# openSX70_SONAR-FBW_8-9-3-8-S4-TCS3200-NO.net
KiCad netlist of a schematic drawn in EAGLE
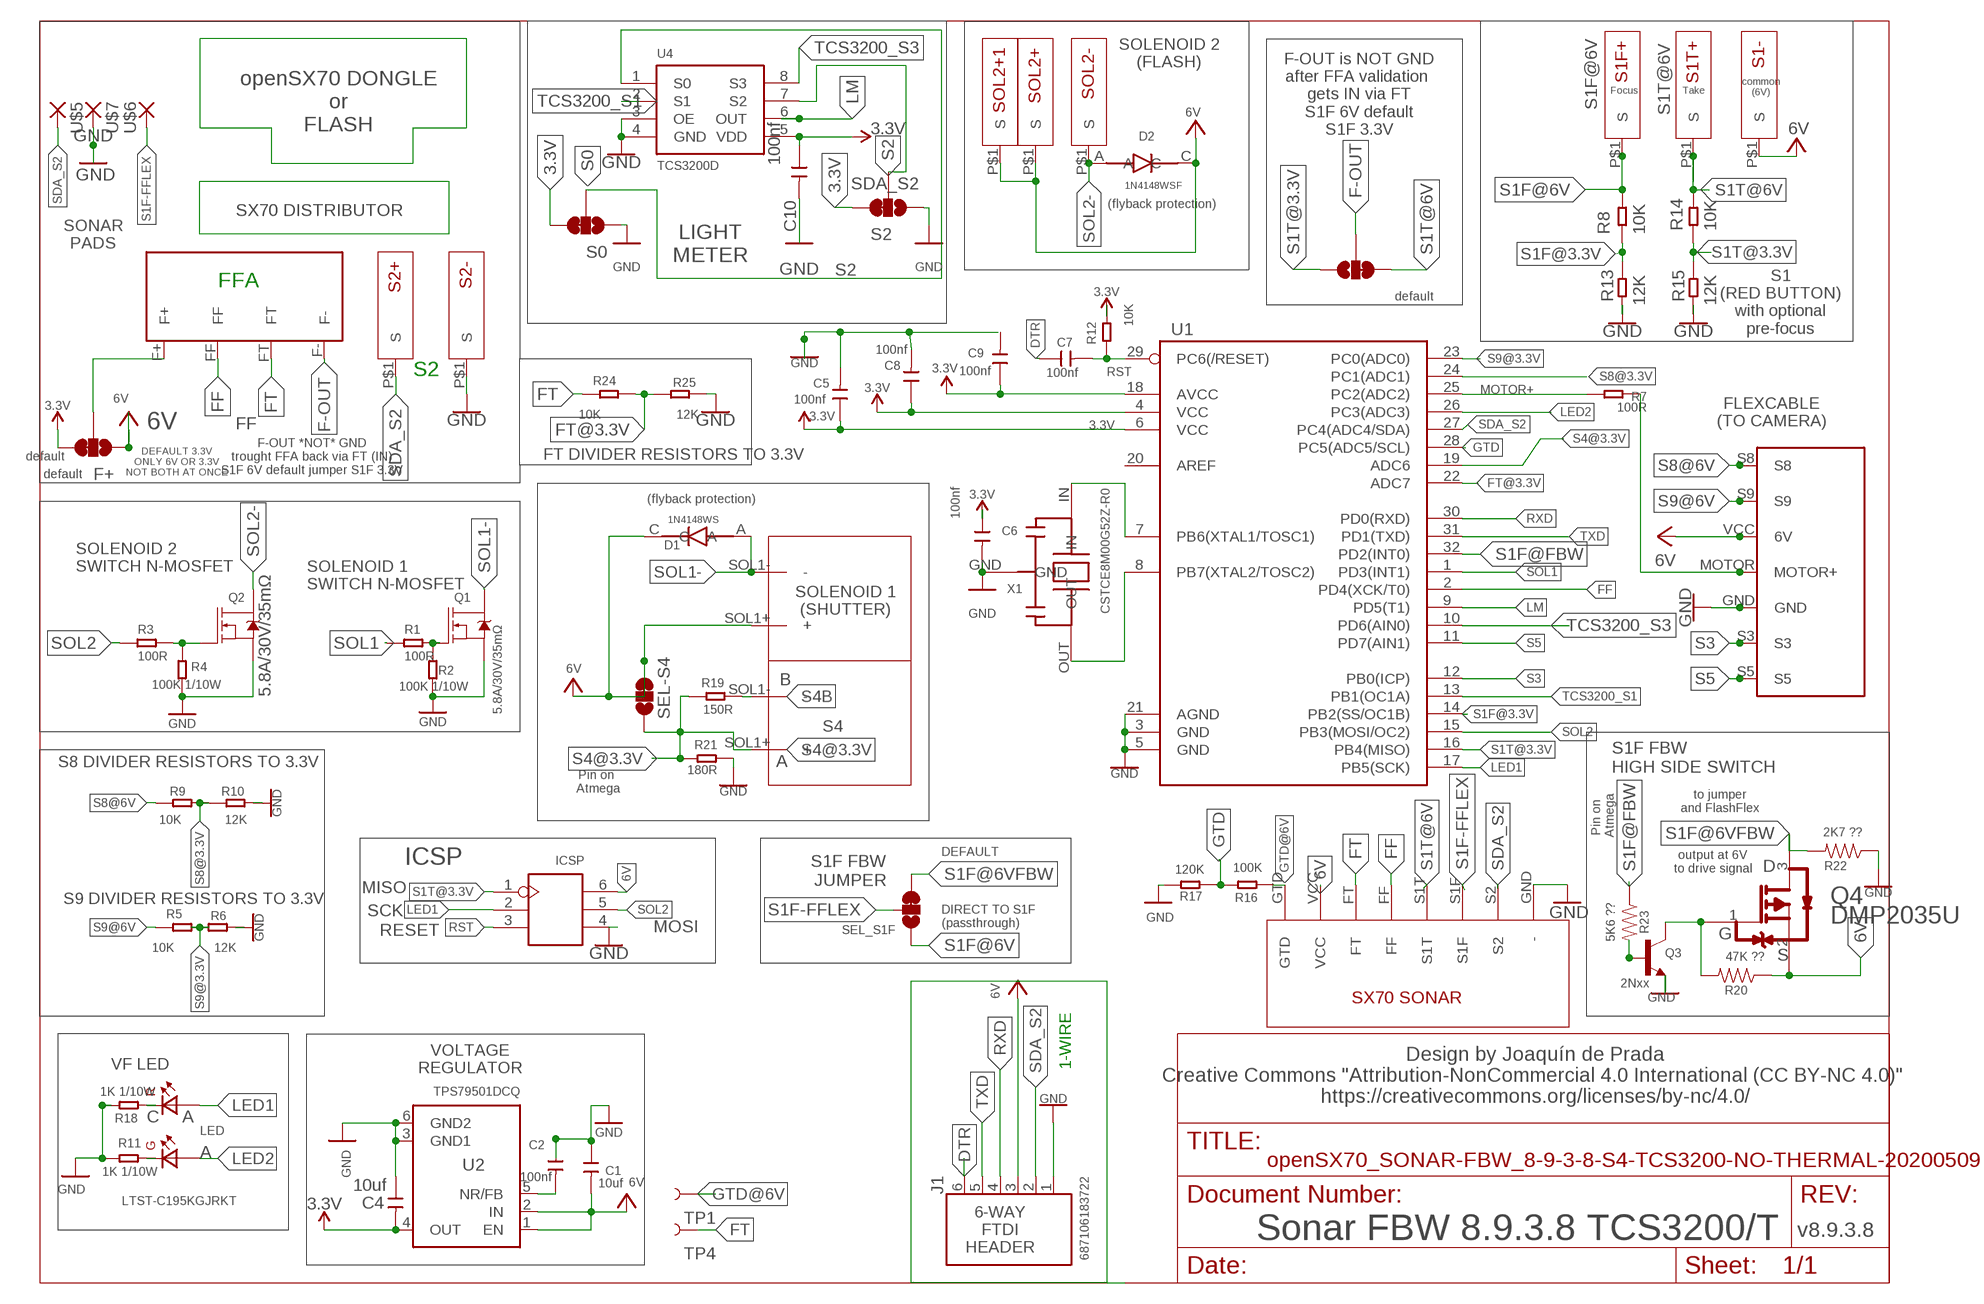
[diagram p0: schematic, sheet 1]

(export (version "E")
  (design (tool "Eeschema 10.0.6"))
  (components
    (comp (ref "C1")
      (value "10uf")
      (footprint "eagle-import:C0603")
      (fields (field (name "MPN") "CC0603KRX5R6BB106"))
      (libsource (lib "eagle-import") (part "CERAMIC-10UF-10V-10%-X5R(0603)"))
    )
    (comp (ref "C2")
      (value "100nf")
      (footprint "eagle-import:C0603")
      (fields (field (name "MPN") "CC0603KRX7R9BB104"))
      (libsource (lib "eagle-import") (part "CERAMIC-100NF-50V-10%-X7R(0603)"))
    )
    (comp (ref "C4")
      (value "10uf")
      (footprint "eagle-import:C0603")
      (fields (field (name "MPN") "CC0603KRX5R6BB106"))
      (libsource (lib "eagle-import") (part "CERAMIC-10UF-10V-10%-X5R(0603)"))
    )
    (comp (ref "C5")
      (value "100nf")
      (footprint "eagle-import:C0603")
      (fields (field (name "MPN") "CC0603KRX7R9BB104"))
      (libsource (lib "eagle-import") (part "CERAMIC-100NF-50V-10%-X7R(0603)"))
    )
    (comp (ref "C6")
      (value "100nf")
      (footprint "eagle-import:C0603")
      (fields (field (name "MPN") "CC0603KRX7R9BB104"))
      (libsource (lib "eagle-import") (part "CERAMIC-100NF-50V-10%-X7R(0603)"))
    )
    (comp (ref "C7")
      (value "100nf")
      (footprint "eagle-import:C0603")
      (fields (field (name "MPN") "CC0603KRX7R9BB104"))
      (libsource (lib "eagle-import") (part "CERAMIC-100NF-50V-10%-X7R(0603)"))
    )
    (comp (ref "C8")
      (value "100nf")
      (footprint "eagle-import:C0603")
      (fields (field (name "MPN") "CC0603KRX7R9BB104"))
      (libsource (lib "eagle-import") (part "CERAMIC-100NF-50V-10%-X7R(0603)"))
    )
    (comp (ref "C9")
      (value "100nf")
      (footprint "eagle-import:C0603")
      (fields (field (name "MPN") "CC0603KRX7R9BB104"))
      (libsource (lib "eagle-import") (part "CERAMIC-100NF-50V-10%-X7R(0603)"))
    )
    (comp (ref "C10")
      (value "100nf")
      (footprint "eagle-import:C0603")
      (fields (field (name "MPN") "CC0603KRX7R9BB104"))
      (libsource (lib "eagle-import") (part "CERAMIC-100NF-50V-10%-X7R(0603)"))
    )
    (comp (ref "D1")
      (value "1N4148WS")
      (footprint "eagle-import:SODFL2512X100N")
      (fields (field (name "MANUFACTURER") "Fairchild Semiconductor"))
      (libsource (lib "eagle-import") (part "1N4148WS"))
    )
    (comp (ref "D2")
      (value "1N4148WSF")
      (footprint "eagle-import:SODFL2512X100N")
      (fields (field (name "MANUFACTURER") "Fairchild Semiconductor"))
      (libsource (lib "eagle-import") (part "1N4148WS"))
    )
    (comp (ref "F+")
      (value "S0")
      (footprint "eagle-import:SMT-JUMPER_3_1-NC_TRACE_SILK")
      (libsource (lib "eagle-import") (part "JUMPER-SMT_3_1-NC_TRACE_SILK"))
    )
    (comp (ref "ICSP")
      (value "ICSP")
      (footprint "eagle-import:H2X3-2.54")
      (libsource (lib "eagle-import") (part "ICSP"))
    )
    (comp (ref "J1")
      (value "687106183722")
      (footprint "eagle-import:687106183722")
      (fields (field (name "MF") "Wurth Electronics"))
      (libsource (lib "eagle-import") (part "687106183722"))
    )
    (comp (ref "LED")
      (value "LTST-C195KGJRKT")
      (footprint "eagle-import:LTST-BILED-15X16")
      (fields (field (name "MF") "Lite-On Inc."))
      (libsource (lib "eagle-import") (part "LTST-C195KGJRKT"))
    )
    (comp (ref "Q1")
      (value "5.8A/30V/35mΩ")
      (footprint "eagle-import:SOT23-3")
      (libsource (lib "eagle-import") (part "MOSFET-NCH-AO3404A"))
    )
    (comp (ref "Q2")
      (value "5.8A/30V/35mΩ")
      (footprint "eagle-import:SOT23-3")
      (libsource (lib "eagle-import") (part "MOSFET-NCH-AO3404A"))
    )
    (comp (ref "Q3")
      (value "BFR93-NPN-SOT23-BEC")
      (footprint "eagle-import:SOT23-BEC")
      (libsource (lib "eagle-import") (part "-NPN-SOT23-BECBFR93"))
    )
    (comp (ref "Q4")
      (value "DIODES_INC._DMP2035UDIODES_INC._DMP2035U_0_2")
      (footprint "eagle-import:DIODES_INC._DMP2035U_2")
      (fields
        (field (name "DIGIKEY_PART_NUMBER") "DMP2035U-7DICT-ND")
        (field (name "MF") "Diodes Inc.")
        (field (name "MOUSER_PART_NUMBER") "621-DMP2035U-7")
      )
      (libsource (lib "eagle-import") (part "DIODES_INC._DMP2035UDIODES_INC._DMP2035U_0_2"))
    )
    (comp (ref "R1")
      (value "100R")
      (footprint "eagle-import:R0603")
      (fields (field (name "MPN") "RC0603JR-07100RL"))
      (libsource (lib "eagle-import") (part "SMD-RES-100R-5%-1/10W(0603)"))
    )
    (comp (ref "R2")
      (value "100K 1/10W")
      (footprint "eagle-import:R0603")
      (fields (field (name "MPN") "RC0603JR-07100KL"))
      (libsource (lib "eagle-import") (part "SMD-RES-100K-5%-1/10W(0603)"))
    )
    (comp (ref "R3")
      (value "100R")
      (footprint "eagle-import:R0603")
      (fields (field (name "MPN") "RC0603JR-07100RL"))
      (libsource (lib "eagle-import") (part "SMD-RES-100R-5%-1/10W(0603)"))
    )
    (comp (ref "R4")
      (value "100K 1/10W")
      (footprint "eagle-import:R0603")
      (fields (field (name "MPN") "RC0603JR-07100KL"))
      (libsource (lib "eagle-import") (part "SMD-RES-100K-5%-1/10W(0603)"))
    )
    (comp (ref "R5")
      (value "10K")
      (footprint "eagle-import:R0603")
      (fields (field (name "MPN") "RC0603FR-0715KL"))
      (libsource (lib "eagle-import") (part "SMD-RES-15K-1%-1/10W(0603)"))
    )
    (comp (ref "R6")
      (value "12K")
      (footprint "eagle-import:R0603")
      (fields (field (name "MPN") "RC0603FR-0710KL"))
      (libsource (lib "eagle-import") (part "SMD-RES-10K-1%-1/10W(0603)"))
    )
    (comp (ref "R7")
      (value "100R")
      (footprint "eagle-import:R0603")
      (fields (field (name "MPN") "RC0603JR-07100RL"))
      (libsource (lib "eagle-import") (part "SMD-RES-100R-5%-1/10W(0603)"))
    )
    (comp (ref "R8")
      (value "10K")
      (footprint "eagle-import:R0603")
      (fields (field (name "MPN") "RC0603FR-0710KL"))
      (libsource (lib "eagle-import") (part "SMD-RES-10K-1%-1/10W(0603)"))
    )
    (comp (ref "R9")
      (value "10K")
      (footprint "eagle-import:R0603")
      (fields (field (name "MPN") "RC0603FR-0715KL"))
      (libsource (lib "eagle-import") (part "SMD-RES-15K-1%-1/10W(0603)"))
    )
    (comp (ref "R10")
      (value "12K")
      (footprint "eagle-import:R0603")
      (fields (field (name "MPN") "RC0603FR-0710KL"))
      (libsource (lib "eagle-import") (part "SMD-RES-10K-1%-1/10W(0603)"))
    )
    (comp (ref "R11")
      (value "1K 1/10W")
      (footprint "eagle-import:R0603")
      (fields (field (name "MPN") "RC0603JR-071KL"))
      (libsource (lib "eagle-import") (part "SMD-RES-1K-5%-1/10W(0603)"))
    )
    (comp (ref "R12")
      (value "10K")
      (footprint "eagle-import:R0603")
      (fields (field (name "MPN") "RC0603FR-0710KL"))
      (libsource (lib "eagle-import") (part "SMD-RES-10K-1%-1/10W(0603)"))
    )
    (comp (ref "R13")
      (value "12K")
      (footprint "eagle-import:R0603")
      (fields (field (name "MPN") "RC0603FR-0715KL"))
      (libsource (lib "eagle-import") (part "SMD-RES-15K-1%-1/10W(0603)"))
    )
    (comp (ref "R14")
      (value "10K")
      (footprint "eagle-import:R0603")
      (fields (field (name "MPN") "RC0603FR-0710KL"))
      (libsource (lib "eagle-import") (part "SMD-RES-10K-1%-1/10W(0603)"))
    )
    (comp (ref "R15")
      (value "12K")
      (footprint "eagle-import:R0603")
      (fields (field (name "MPN") "RC0603FR-0715KL"))
      (libsource (lib "eagle-import") (part "SMD-RES-15K-1%-1/10W(0603)"))
    )
    (comp (ref "R16")
      (value "100K")
      (footprint "eagle-import:R0603")
      (fields (field (name "MPN") "RC0603FR-0710KL"))
      (libsource (lib "eagle-import") (part "SMD-RES-10K-1%-1/10W(0603)"))
    )
    (comp (ref "R17")
      (value "120K")
      (footprint "eagle-import:R0603")
      (fields (field (name "MPN") "RC0603FR-0715KL"))
      (libsource (lib "eagle-import") (part "SMD-RES-15K-1%-1/10W(0603)"))
    )
    (comp (ref "R18")
      (value "1K 1/10W")
      (footprint "eagle-import:R0603")
      (fields (field (name "MPN") "RC0603JR-071KL"))
      (libsource (lib "eagle-import") (part "SMD-RES-1K-5%-1/10W(0603)"))
    )
    (comp (ref "R19")
      (value "150R")
      (footprint "eagle-import:R0603")
      (fields (field (name "MPN") "RC0603FR-0710KL"))
      (libsource (lib "eagle-import") (part "SMD-RES-10K-1%-1/10W(0603)"))
    )
    (comp (ref "R20")
      (value "47K")
      (footprint "eagle-import:0603")
      (libsource (lib "eagle-import") (part "RESISTOR0603"))
    )
    (comp (ref "R21")
      (value "180R")
      (footprint "eagle-import:R0603")
      (fields (field (name "MPN") "RC0603FR-0710KL"))
      (libsource (lib "eagle-import") (part "SMD-RES-10K-1%-1/10W(0603)"))
    )
    (comp (ref "R22")
      (value "2K7")
      (footprint "eagle-import:0603")
      (libsource (lib "eagle-import") (part "RESISTOR0603"))
    )
    (comp (ref "R23")
      (value "47K")
      (footprint "eagle-import:0603")
      (libsource (lib "eagle-import") (part "RESISTOR0603"))
    )
    (comp (ref "R24")
      (value "10K")
      (footprint "eagle-import:R0603")
      (fields (field (name "MPN") "RC0603FR-0715KL"))
      (libsource (lib "eagle-import") (part "SMD-RES-15K-1%-1/10W(0603)"))
    )
    (comp (ref "R25")
      (value "12K")
      (footprint "eagle-import:R0603")
      (fields (field (name "MPN") "RC0603FR-0710KL"))
      (libsource (lib "eagle-import") (part "SMD-RES-10K-1%-1/10W(0603)"))
    )
    (comp (ref "S0")
      (value "S0")
      (footprint "eagle-import:SMT-JUMPER_3_1-NC_TRACE_SILK")
      (libsource (lib "eagle-import") (part "JUMPER-SMT_3_1-NC_TRACE_SILK"))
    )
    (comp (ref "S1-")
      (value "SX70-S-PAD-NEW")
      (footprint "eagle-import:SX70-S-PAD2")
      (libsource (lib "eagle-import") (part "SX70-S-PAD-NEW"))
    )
    (comp (ref "S1F+")
      (value "SX70-S-PAD-NEW")
      (footprint "eagle-import:SX70-S-PAD2")
      (libsource (lib "eagle-import") (part "SX70-S-PAD-NEW"))
    )
    (comp (ref "S1T+")
      (value "SX70-S-PAD-NEW")
      (footprint "eagle-import:SX70-S-PAD2")
      (libsource (lib "eagle-import") (part "SX70-S-PAD-NEW"))
    )
    (comp (ref "S2")
      (value "S2")
      (footprint "eagle-import:SMT-JUMPER_3_1-NC_TRACE_SILK")
      (libsource (lib "eagle-import") (part "JUMPER-SMT_3_1-NC_TRACE_SILK"))
    )
    (comp (ref "S2+")
      (value "SX70-S-PAD-NEW")
      (footprint "eagle-import:SX70-S-PAD2")
      (libsource (lib "eagle-import") (part "SX70-S-PAD-NEW"))
    )
    (comp (ref "S2-")
      (value "SX70-S-PAD-NEW")
      (footprint "eagle-import:SX70-S-PAD2")
      (libsource (lib "eagle-import") (part "SX70-S-PAD-NEW"))
    )
    (comp (ref "S4")
      (value "SX70-SOLENOID1-2PADS")
      (footprint "eagle-import:SX70-SOLENOID1-2")
      (libsource (lib "eagle-import") (part "SX70-SOLENOID1-2PADS"))
    )
    (comp (ref "SEL_F-")
      (value "SEL-S4")
      (footprint "eagle-import:SMT-JUMPER_3_1-NC_TRACE_SILK")
      (libsource (lib "eagle-import") (part "JUMPER-SMT_3_1-NC_TRACE_SILK"))
    )
    (comp (ref "SEL_S1F")
      (value "SEL-S4")
      (footprint "eagle-import:SMT-JUMPER_3_1-NC_TRACE_SILK")
      (libsource (lib "eagle-import") (part "JUMPER-SMT_3_1-NC_TRACE_SILK"))
    )
    (comp (ref "SEL_S4")
      (value "SEL-S4")
      (footprint "eagle-import:SMT-JUMPER_3_1-NC_TRACE_SILK")
      (libsource (lib "eagle-import") (part "JUMPER-SMT_3_1-NC_TRACE_SILK"))
    )
    (comp (ref "SOL1")
      (value "SX70-SOLENOID1-2PADS")
      (footprint "eagle-import:SX70-SOLENOID1-2")
      (libsource (lib "eagle-import") (part "SX70-SOLENOID1-2PADS"))
    )
    (comp (ref "SOL2+")
      (value "SX70-S-PAD-NEW")
      (footprint "eagle-import:SX70-S-PAD2")
      (libsource (lib "eagle-import") (part "SX70-S-PAD-NEW"))
    )
    (comp (ref "SOL2+1")
      (value "SX70-S-PAD-NEW")
      (footprint "eagle-import:SX70-S-PAD2")
      (libsource (lib "eagle-import") (part "SX70-S-PAD-NEW"))
    )
    (comp (ref "SOL2-")
      (value "SX70-S-PAD-NEW")
      (footprint "eagle-import:SX70-S-PAD2")
      (libsource (lib "eagle-import") (part "SX70-S-PAD-NEW"))
    )
    (comp (ref "TP1")
      (value "TEST-POINT3X4")
      (footprint "eagle-import:PAD.03X.04")
      (libsource (lib "eagle-import") (part "TEST-POINT3X4"))
    )
    (comp (ref "TP4")
      (value "TEST-POINT3X4")
      (footprint "eagle-import:PAD.03X.04")
      (libsource (lib "eagle-import") (part "TEST-POINT3X4"))
    )
    (comp (ref "U$1")
      (value "SX70-7-PAD")
      (footprint "eagle-import:SX70-7-PAD-PROPER")
      (libsource (lib "eagle-import") (part "SX70-7-PAD"))
    )
    (comp (ref "U$2")
      (value "FFA")
      (footprint "eagle-import:FFA-PAD-PACKAGE")
      (libsource (lib "eagle-import") (part "SX70-FFA-PAD"))
    )
    (comp (ref "U$3")
      (value "SX70-SONAR-FLASHFLEX")
      (footprint "eagle-import:SONAR-FLASHFLEX")
      (libsource (lib "eagle-import") (part "SX70-SONAR-FLASHFLEX"))
    )
    (comp (ref "U$5")
      (value "S2-SONAR")
      (footprint "eagle-import:S2-SONAR")
      (libsource (lib "eagle-import") (part "S2-SONAR"))
    )
    (comp (ref "U$6")
      (value "S1F@6V")
      (footprint "eagle-import:S2-SONAR")
      (libsource (lib "eagle-import") (part "S2-SONAR"))
    )
    (comp (ref "U$7")
      (value "GND-SONAR")
      (footprint "eagle-import:GND-SONAR")
      (libsource (lib "eagle-import") (part "GND-SONAR"))
    )
    (comp (ref "U1")
      (value "ATMEGA328P_32MLFATMEGA328-MLF")
      (footprint "eagle-import:MLF32")
      (libsource (lib "eagle-import") (part "ATMEGA328P_32MLFATMEGA328-MLF"))
    )
    (comp (ref "U2")
      (value "TPS79501DCQ")
      (footprint "eagle-import:SOT127P706X180-6N")
      (fields (field (name "DIGI-KEY_PART_NUMBER") "296-27102-5-ND") (field (name "MF") "Texas Instruments"))
      (libsource (lib "eagle-import") (part "TPS79501DCQ"))
    )
    (comp (ref "U4")
      (value "TCS3200D")
      (footprint "eagle-import:SOIC8")
      (fields (field (name "MF") "ams") (field (name "MP") "TCS3200D-TR"))
      (libsource (lib "eagle-import") (part "TCS3200D"))
    )
    (comp (ref "X1")
      (value "CSTCE8M00G52Z-R0")
      (footprint "eagle-import:CFP95P160X100-3N")
      (fields (field (name "MF") "Murata") (field (name "MP") "CSTCE16M0V53-R0"))
      (libsource (lib "eagle-import") (part "CSTCE16M0V53-R0"))
    )
  )
  (nets
    (net (code "1") (name "/MOTOR+") (class "Default")
      (node (ref "R7") (pin "1") (pinfunction "1_1") (pintype "passive"))
      (node (ref "U1") (pin "25") (pinfunction "PC2(ADC2)_25") (pintype "bidirectional"))
    )
    (net (code "2") (name "3.3V") (class "Default")
      (node (ref "C10") (pin "1") (pinfunction "1_1") (pintype "passive"))
      (node (ref "C4") (pin "2") (pinfunction "2_2") (pintype "passive"))
      (node (ref "C5") (pin "1") (pinfunction "1_1") (pintype "passive"))
      (node (ref "C6") (pin "1") (pinfunction "1_1") (pintype "passive"))
      (node (ref "C8") (pin "1") (pinfunction "1_1") (pintype "passive"))
      (node (ref "C9") (pin "1") (pinfunction "1_1") (pintype "passive"))
      (node (ref "F+") (pin "3") (pinfunction "3_3") (pintype "passive"))
      (node (ref "R12") (pin "2") (pinfunction "2_2") (pintype "passive"))
      (node (ref "S0") (pin "3") (pinfunction "3_3") (pintype "passive"))
      (node (ref "S2") (pin "3") (pinfunction "3_3") (pintype "passive"))
      (node (ref "U1") (pin "18") (pinfunction "AVCC_18") (pintype "bidirectional"))
      (node (ref "U1") (pin "4") (pinfunction "VCC_4") (pintype "bidirectional"))
      (node (ref "U1") (pin "6") (pinfunction "VCC_6") (pintype "bidirectional"))
      (node (ref "U2") (pin "4") (pinfunction "OUT_4") (pintype "output"))
      (node (ref "U4") (pin "5") (pinfunction "VDD_5") (pintype "bidirectional"))
    )
    (net (code "3") (name "6V") (class "Default")
      (node (ref "C1") (pin "2") (pinfunction "2_2") (pintype "passive"))
      (node (ref "D1") (pin "C") (pinfunction "C_C") (pintype "passive"))
      (node (ref "D2") (pin "C") (pinfunction "C_C") (pintype "passive"))
      (node (ref "F+") (pin "1") (pinfunction "1_1") (pintype "passive"))
      (node (ref "ICSP") (pin "6") (pinfunction "VCC_6") (pintype "bidirectional"))
      (node (ref "J1") (pin "3") (pinfunction "4_3") (pintype "passive"))
      (node (ref "Q4") (pin "2") (pinfunction "S_2") (pintype "passive"))
      (node (ref "R20") (pin "1") (pinfunction "1_1") (pintype "passive"))
      (node (ref "S1-") (pin "P$1") (pinfunction "S_P$1") (pintype "bidirectional"))
      (node (ref "SEL_S4") (pin "2") (pinfunction "2_2") (pintype "passive"))
      (node (ref "SEL_S4") (pin "3") (pinfunction "3_3") (pintype "passive"))
      (node (ref "SOL1") (pin "SOL1+") (pinfunction "+_SOL1+") (pintype "bidirectional"))
      (node (ref "SOL2+") (pin "P$1") (pinfunction "S_P$1") (pintype "bidirectional"))
      (node (ref "SOL2+1") (pin "P$1") (pinfunction "S_P$1") (pintype "bidirectional"))
      (node (ref "U$1") (pin "VCC") (pinfunction "6V_VCC") (pintype "bidirectional"))
      (node (ref "U$3") (pin "VCC") (pinfunction "VCC_VCC") (pintype "bidirectional"))
      (node (ref "U2") (pin "1") (pinfunction "EN_1") (pintype "input"))
      (node (ref "U2") (pin "2") (pinfunction "IN_2") (pintype "input"))
    )
    (net (code "4") (name "DTR") (class "Default")
      (node (ref "C7") (pin "1") (pinfunction "1_1") (pintype "passive"))
      (node (ref "J1") (pin "6") (pinfunction "1_6") (pintype "passive"))
    )
    (net (code "5") (name "F-OUT") (class "Default")
      (node (ref "SEL_F-") (pin "2") (pinfunction "2_2") (pintype "passive"))
      (node (ref "U$2") (pin "F-") (pinfunction "F-_F-") (pintype "bidirectional"))
    )
    (net (code "6") (name "FF") (class "Default")
      (node (ref "U$2") (pin "FF") (pinfunction "FF_FF") (pintype "bidirectional"))
      (node (ref "U$3") (pin "FF") (pinfunction "FF_FF") (pintype "bidirectional"))
      (node (ref "U1") (pin "2") (pinfunction "PD4(XCK/T0)_2") (pintype "bidirectional"))
    )
    (net (code "7") (name "FT") (class "Default")
      (node (ref "R24") (pin "1") (pinfunction "1_1") (pintype "passive"))
      (node (ref "TP4") (pin "P$1") (pinfunction "1_P$1") (pintype "bidirectional"))
      (node (ref "U$2") (pin "FT") (pinfunction "FT_FT") (pintype "bidirectional"))
      (node (ref "U$3") (pin "FT") (pinfunction "FT_FT") (pintype "bidirectional"))
    )
    (net (code "8") (name "FT@3.3V") (class "Default")
      (node (ref "R24") (pin "2") (pinfunction "2_2") (pintype "passive"))
      (node (ref "R25") (pin "1") (pinfunction "1_1") (pintype "passive"))
      (node (ref "U1") (pin "22") (pinfunction "ADC7_22") (pintype "bidirectional"))
    )
    (net (code "9") (name "GND") (class "Default")
      (node (ref "C1") (pin "1") (pinfunction "1_1") (pintype "passive"))
      (node (ref "C10") (pin "2") (pinfunction "2_2") (pintype "passive"))
      (node (ref "C2") (pin "1") (pinfunction "1_1") (pintype "passive"))
      (node (ref "C4") (pin "1") (pinfunction "1_1") (pintype "passive"))
      (node (ref "C5") (pin "2") (pinfunction "2_2") (pintype "passive"))
      (node (ref "C6") (pin "2") (pinfunction "2_2") (pintype "passive"))
      (node (ref "C8") (pin "2") (pinfunction "2_2") (pintype "passive"))
      (node (ref "ICSP") (pin "4") (pinfunction "GND_4") (pintype "bidirectional"))
      (node (ref "J1") (pin "1") (pinfunction "6_1") (pintype "passive"))
      (node (ref "Q1") (pin "2") (pinfunction "S_2") (pintype "bidirectional"))
      (node (ref "Q2") (pin "2") (pinfunction "S_2") (pintype "bidirectional"))
      (node (ref "Q3") (pin "E") (pinfunction "E_E") (pintype "passive"))
      (node (ref "R10") (pin "2") (pinfunction "2_2") (pintype "passive"))
      (node (ref "R11") (pin "1") (pinfunction "1_1") (pintype "passive"))
      (node (ref "R13") (pin "1") (pinfunction "1_1") (pintype "passive"))
      (node (ref "R15") (pin "1") (pinfunction "1_1") (pintype "passive"))
      (node (ref "R17") (pin "1") (pinfunction "1_1") (pintype "passive"))
      (node (ref "R18") (pin "2") (pinfunction "2_2") (pintype "passive"))
      (node (ref "R2") (pin "1") (pinfunction "1_1") (pintype "passive"))
      (node (ref "R21") (pin "1") (pinfunction "1_1") (pintype "passive"))
      (node (ref "R22") (pin "1") (pinfunction "1_1") (pintype "passive"))
      (node (ref "R25") (pin "2") (pinfunction "2_2") (pintype "passive"))
      (node (ref "R4") (pin "1") (pinfunction "1_1") (pintype "passive"))
      (node (ref "R6") (pin "2") (pinfunction "2_2") (pintype "passive"))
      (node (ref "S0") (pin "1") (pinfunction "1_1") (pintype "passive"))
      (node (ref "S2") (pin "1") (pinfunction "1_1") (pintype "passive"))
      (node (ref "S2-") (pin "P$1") (pinfunction "S_P$1") (pintype "bidirectional"))
      (node (ref "U$1") (pin "GND") (pinfunction "GND_GND") (pintype "bidirectional"))
      (node (ref "U$3") (pin "GND") (pinfunction "-_GND") (pintype "bidirectional"))
      (node (ref "U$7") (pin "GND-SONAR") (pinfunction "P_GND-SONAR") (pintype "passive"))
      (node (ref "U1") (pin "21") (pinfunction "AGND_21") (pintype "bidirectional"))
      (node (ref "U1") (pin "3") (pinfunction "GND_3") (pintype "bidirectional"))
      (node (ref "U1") (pin "5") (pinfunction "GND_5") (pintype "bidirectional"))
      (node (ref "U2") (pin "3") (pinfunction "GND1_3") (pintype "power_in"))
      (node (ref "U2") (pin "6") (pinfunction "GND2_6") (pintype "power_in"))
      (node (ref "U4") (pin "3") (pinfunction "OE_3") (pintype "bidirectional"))
      (node (ref "U4") (pin "4") (pinfunction "GND_4") (pintype "bidirectional"))
      (node (ref "X1") (pin "GND") (pinfunction "GND_GND") (pintype "passive"))
    )
    (net (code "10") (name "GTD") (class "Default")
      (node (ref "R16") (pin "2") (pinfunction "2_2") (pintype "passive"))
      (node (ref "R17") (pin "2") (pinfunction "2_2") (pintype "passive"))
      (node (ref "U1") (pin "28") (pinfunction "PC5(ADC5/SCL)_28") (pintype "bidirectional"))
    )
    (net (code "11") (name "GTD@6V") (class "Default")
      (node (ref "R16") (pin "1") (pinfunction "1_1") (pintype "passive"))
      (node (ref "TP1") (pin "P$1") (pinfunction "1_P$1") (pintype "bidirectional"))
      (node (ref "U$3") (pin "GTD") (pinfunction "GTD_GTD") (pintype "bidirectional"))
    )
    (net (code "12") (name "LED1") (class "Default")
      (node (ref "ICSP") (pin "2") (pinfunction "SCK_2") (pintype "bidirectional"))
      (node (ref "LED") (pin "P$2") (pinfunction "A2_P$2") (pintype "passive"))
      (node (ref "U1") (pin "17") (pinfunction "PB5(SCK)_17") (pintype "bidirectional"))
    )
    (net (code "13") (name "LED2") (class "Default")
      (node (ref "LED") (pin "P$1") (pinfunction "A1_P$1") (pintype "passive"))
      (node (ref "U1") (pin "26") (pinfunction "PC3(ADC3)_26") (pintype "bidirectional"))
    )
    (net (code "14") (name "LM") (class "Default")
      (node (ref "U1") (pin "9") (pinfunction "PD5(T1)_9") (pintype "bidirectional"))
      (node (ref "U4") (pin "6") (pinfunction "OUT_6") (pintype "bidirectional"))
    )
    (net (code "15") (name "Net-(F+-Pad2)") (class "Default")
      (node (ref "F+") (pin "2") (pinfunction "2_2") (pintype "passive"))
      (node (ref "U$2") (pin "F+") (pinfunction "F+_F+") (pintype "bidirectional"))
    )
    (net (code "16") (name "Net-(LED-K1)") (class "Default")
      (node (ref "LED") (pin "P$3") (pinfunction "K1_P$3") (pintype "passive"))
      (node (ref "R11") (pin "2") (pinfunction "2_2") (pintype "passive"))
    )
    (net (code "17") (name "Net-(LED-K2)") (class "Default")
      (node (ref "LED") (pin "P$4") (pinfunction "K2_P$4") (pintype "passive"))
      (node (ref "R18") (pin "1") (pinfunction "1_1") (pintype "passive"))
    )
    (net (code "18") (name "Net-(Q1-G)") (class "Default")
      (node (ref "Q1") (pin "1") (pinfunction "G_1") (pintype "bidirectional"))
      (node (ref "R1") (pin "2") (pinfunction "2_2") (pintype "passive"))
      (node (ref "R2") (pin "2") (pinfunction "2_2") (pintype "passive"))
    )
    (net (code "19") (name "Net-(Q2-G)") (class "Default")
      (node (ref "Q2") (pin "1") (pinfunction "G_1") (pintype "bidirectional"))
      (node (ref "R3") (pin "2") (pinfunction "2_2") (pintype "passive"))
      (node (ref "R4") (pin "2") (pinfunction "2_2") (pintype "passive"))
    )
    (net (code "20") (name "Net-(Q3-PadB)") (class "Default")
      (node (ref "Q3") (pin "B") (pinfunction "B_B") (pintype "passive"))
      (node (ref "R23") (pin "2") (pinfunction "2_2") (pintype "passive"))
    )
    (net (code "21") (name "Net-(Q4-G)") (class "Default")
      (node (ref "Q3") (pin "C") (pinfunction "C_C") (pintype "passive"))
      (node (ref "Q4") (pin "1") (pinfunction "G_1") (pintype "passive"))
      (node (ref "R20") (pin "2") (pinfunction "2_2") (pintype "passive"))
    )
    (net (code "22") (name "Net-(U$1-MOTOR+)") (class "Default")
      (node (ref "R7") (pin "2") (pinfunction "2_2") (pintype "passive"))
      (node (ref "U$1") (pin "MOTOR") (pinfunction "MOTOR+_MOTOR") (pintype "bidirectional"))
    )
    (net (code "23") (name "Net-(U1-PB6(XTAL1{slash}TOSC1))") (class "Default")
      (node (ref "U1") (pin "7") (pinfunction "PB6(XTAL1/TOSC1)_7") (pintype "bidirectional"))
      (node (ref "X1") (pin "IN") (pinfunction "IN_IN") (pintype "input"))
    )
    (net (code "24") (name "Net-(U1-PB7(XTAL2{slash}TOSC2))") (class "Default")
      (node (ref "U1") (pin "8") (pinfunction "PB7(XTAL2/TOSC2)_8") (pintype "bidirectional"))
      (node (ref "X1") (pin "OUT") (pinfunction "OUT_OUT") (pintype "output"))
    )
    (net (code "25") (name "Net-(U2-NR{slash}FB)") (class "Default")
      (node (ref "C2") (pin "2") (pinfunction "2_2") (pintype "passive"))
      (node (ref "U2") (pin "5") (pinfunction "NR/FB_5") (pintype "input"))
    )
    (net (code "26") (name "RST") (class "Default")
      (node (ref "C7") (pin "2") (pinfunction "2_2") (pintype "passive"))
      (node (ref "ICSP") (pin "3") (pinfunction "RST_3") (pintype "bidirectional"))
      (node (ref "R12") (pin "1") (pinfunction "1_1") (pintype "passive"))
      (node (ref "U1") (pin "29") (pinfunction "PC6(/RESET)_29") (pintype "bidirectional"))
    )
    (net (code "27") (name "RXD") (class "Default")
      (node (ref "J1") (pin "4") (pinfunction "3_4") (pintype "passive"))
      (node (ref "U1") (pin "30") (pinfunction "PD0(RXD)_30") (pintype "bidirectional"))
    )
    (net (code "28") (name "S0") (class "Default")
      (node (ref "S0") (pin "2") (pinfunction "2_2") (pintype "passive"))
      (node (ref "U4") (pin "1") (pinfunction "S0_1") (pintype "bidirectional"))
    )
    (net (code "29") (name "S1F-FFLEX") (class "Default")
      (node (ref "SEL_S1F") (pin "2") (pinfunction "2_2") (pintype "passive"))
      (node (ref "U$3") (pin "S1F") (pinfunction "S1F_S1F") (pintype "bidirectional"))
      (node (ref "U$6") (pin "S2-SONAR") (pinfunction "P_S2-SONAR") (pintype "passive"))
    )
    (net (code "30") (name "S1F@3.3V") (class "Default")
      (node (ref "R13") (pin "2") (pinfunction "2_2") (pintype "passive"))
      (node (ref "R8") (pin "1") (pinfunction "1_1") (pintype "passive"))
      (node (ref "U1") (pin "14") (pinfunction "PB2(SS/OC1B)_14") (pintype "bidirectional"))
    )
    (net (code "31") (name "S1F@6V") (class "Default")
      (node (ref "R8") (pin "2") (pinfunction "2_2") (pintype "passive"))
      (node (ref "S1F+") (pin "P$1") (pinfunction "S_P$1") (pintype "bidirectional"))
      (node (ref "SEL_S1F") (pin "1") (pinfunction "1_1") (pintype "passive"))
    )
    (net (code "32") (name "S1F@6VFBW") (class "Default")
      (node (ref "Q4") (pin "3") (pinfunction "D_3") (pintype "passive"))
      (node (ref "R22") (pin "2") (pinfunction "2_2") (pintype "passive"))
      (node (ref "SEL_S1F") (pin "3") (pinfunction "3_3") (pintype "passive"))
    )
    (net (code "33") (name "S1F@FBW") (class "Default")
      (node (ref "R23") (pin "1") (pinfunction "1_1") (pintype "passive"))
      (node (ref "U1") (pin "32") (pinfunction "PD2(INT0)_32") (pintype "bidirectional"))
    )
    (net (code "34") (name "S1T@3.3V") (class "Default")
      (node (ref "ICSP") (pin "1") (pinfunction "MISO_1") (pintype "bidirectional"))
      (node (ref "R14") (pin "1") (pinfunction "1_1") (pintype "passive"))
      (node (ref "R15") (pin "2") (pinfunction "2_2") (pintype "passive"))
      (node (ref "SEL_F-") (pin "1") (pinfunction "1_1") (pintype "passive"))
      (node (ref "U1") (pin "16") (pinfunction "PB4(MISO)_16") (pintype "bidirectional"))
    )
    (net (code "35") (name "S1T@6V") (class "Default")
      (node (ref "R14") (pin "2") (pinfunction "2_2") (pintype "passive"))
      (node (ref "S1T+") (pin "P$1") (pinfunction "S_P$1") (pintype "bidirectional"))
      (node (ref "SEL_F-") (pin "3") (pinfunction "3_3") (pintype "passive"))
      (node (ref "U$3") (pin "S1T") (pinfunction "S1T_S1T") (pintype "bidirectional"))
    )
    (net (code "36") (name "S2") (class "Default")
      (node (ref "S2") (pin "2") (pinfunction "2_2") (pintype "passive"))
      (node (ref "U4") (pin "7") (pinfunction "S2_7") (pintype "bidirectional"))
    )
    (net (code "37") (name "S3") (class "Default")
      (node (ref "U$1") (pin "S3") (pinfunction "S3_S3") (pintype "bidirectional"))
      (node (ref "U1") (pin "12") (pinfunction "PB0(ICP)_12") (pintype "bidirectional"))
    )
    (net (code "38") (name "S4@3.3V") (class "Default")
      (node (ref "R19") (pin "1") (pinfunction "1_1") (pintype "passive"))
      (node (ref "R21") (pin "2") (pinfunction "2_2") (pintype "passive"))
      (node (ref "S4") (pin "SOL1+") (pinfunction "+_SOL1+") (pintype "bidirectional"))
      (node (ref "SEL_S4") (pin "1") (pinfunction "1_1") (pintype "passive"))
      (node (ref "U1") (pin "19") (pinfunction "ADC6_19") (pintype "bidirectional"))
    )
    (net (code "39") (name "S4B") (class "Default")
      (node (ref "R19") (pin "2") (pinfunction "2_2") (pintype "passive"))
      (node (ref "S4") (pin "SOL1-") (pinfunction "-_SOL1-") (pintype "bidirectional"))
    )
    (net (code "40") (name "S5") (class "Default")
      (node (ref "U$1") (pin "S5") (pinfunction "S5_S5") (pintype "bidirectional"))
      (node (ref "U1") (pin "11") (pinfunction "PD7(AIN1)_11") (pintype "bidirectional"))
    )
    (net (code "41") (name "S8@3.3V") (class "Default")
      (node (ref "R10") (pin "1") (pinfunction "1_1") (pintype "passive"))
      (node (ref "R9") (pin "2") (pinfunction "2_2") (pintype "passive"))
      (node (ref "U1") (pin "24") (pinfunction "PC1(ADC1)_24") (pintype "bidirectional"))
    )
    (net (code "42") (name "S8@6V") (class "Default")
      (node (ref "R9") (pin "1") (pinfunction "1_1") (pintype "passive"))
      (node (ref "U$1") (pin "S8") (pinfunction "S8_S8") (pintype "bidirectional"))
    )
    (net (code "43") (name "S9@3.3V") (class "Default")
      (node (ref "R5") (pin "2") (pinfunction "2_2") (pintype "passive"))
      (node (ref "R6") (pin "1") (pinfunction "1_1") (pintype "passive"))
      (node (ref "U1") (pin "23") (pinfunction "PC0(ADC0)_23") (pintype "bidirectional"))
    )
    (net (code "44") (name "S9@6V") (class "Default")
      (node (ref "R5") (pin "1") (pinfunction "1_1") (pintype "passive"))
      (node (ref "U$1") (pin "S9") (pinfunction "S9_S9") (pintype "bidirectional"))
    )
    (net (code "45") (name "SDA_S2") (class "Default")
      (node (ref "J1") (pin "2") (pinfunction "5_2") (pintype "passive"))
      (node (ref "S2+") (pin "P$1") (pinfunction "S_P$1") (pintype "bidirectional"))
      (node (ref "U$3") (pin "S2") (pinfunction "S2_S2") (pintype "bidirectional"))
      (node (ref "U$5") (pin "S2-SONAR") (pinfunction "P_S2-SONAR") (pintype "passive"))
      (node (ref "U1") (pin "27") (pinfunction "PC4(ADC4/SDA)_27") (pintype "bidirectional"))
    )
    (net (code "46") (name "SOL1") (class "Default")
      (node (ref "R1") (pin "1") (pinfunction "1_1") (pintype "passive"))
      (node (ref "U1") (pin "1") (pinfunction "PD3(INT1)_1") (pintype "bidirectional"))
    )
    (net (code "47") (name "SOL1-") (class "Default")
      (node (ref "D1") (pin "A") (pinfunction "A_A") (pintype "passive"))
      (node (ref "Q1") (pin "3") (pinfunction "D_3") (pintype "bidirectional"))
      (node (ref "SOL1") (pin "SOL1-") (pinfunction "-_SOL1-") (pintype "bidirectional"))
    )
    (net (code "48") (name "SOL2") (class "Default")
      (node (ref "ICSP") (pin "5") (pinfunction "MOSI_5") (pintype "bidirectional"))
      (node (ref "R3") (pin "1") (pinfunction "1_1") (pintype "passive"))
      (node (ref "U1") (pin "15") (pinfunction "PB3(MOSI/OC2)_15") (pintype "bidirectional"))
    )
    (net (code "49") (name "SOL2-") (class "Default")
      (node (ref "D2") (pin "A") (pinfunction "A_A") (pintype "passive"))
      (node (ref "Q2") (pin "3") (pinfunction "D_3") (pintype "bidirectional"))
      (node (ref "SOL2-") (pin "P$1") (pinfunction "S_P$1") (pintype "bidirectional"))
    )
    (net (code "50") (name "TCS3200_S1") (class "Default")
      (node (ref "U1") (pin "13") (pinfunction "PB1(OC1A)_13") (pintype "bidirectional"))
      (node (ref "U4") (pin "2") (pinfunction "S1_2") (pintype "bidirectional"))
    )
    (net (code "51") (name "TCS3200_S3") (class "Default")
      (node (ref "U1") (pin "10") (pinfunction "PD6(AIN0)_10") (pintype "bidirectional"))
      (node (ref "U4") (pin "8") (pinfunction "S3_8") (pintype "bidirectional"))
    )
    (net (code "52") (name "TXD") (class "Default")
      (node (ref "J1") (pin "5") (pinfunction "2_5") (pintype "passive"))
      (node (ref "U1") (pin "31") (pinfunction "PD1(TXD)_31") (pintype "bidirectional"))
    )
    (net (code "53") (name "unconnected-(C9-Pad2)") (class "Default")
      (node (ref "C9") (pin "2") (pinfunction "2_2") (pintype "passive"))
    )
    (net (code "54") (name "unconnected-(U1-AREF-Pad20)") (class "Default")
      (node (ref "U1") (pin "20") (pinfunction "AREF_20") (pintype "bidirectional"))
    )
  )
)
